# rfmacpower.net
KiCad netlist of a schematic drawn in EAGLE
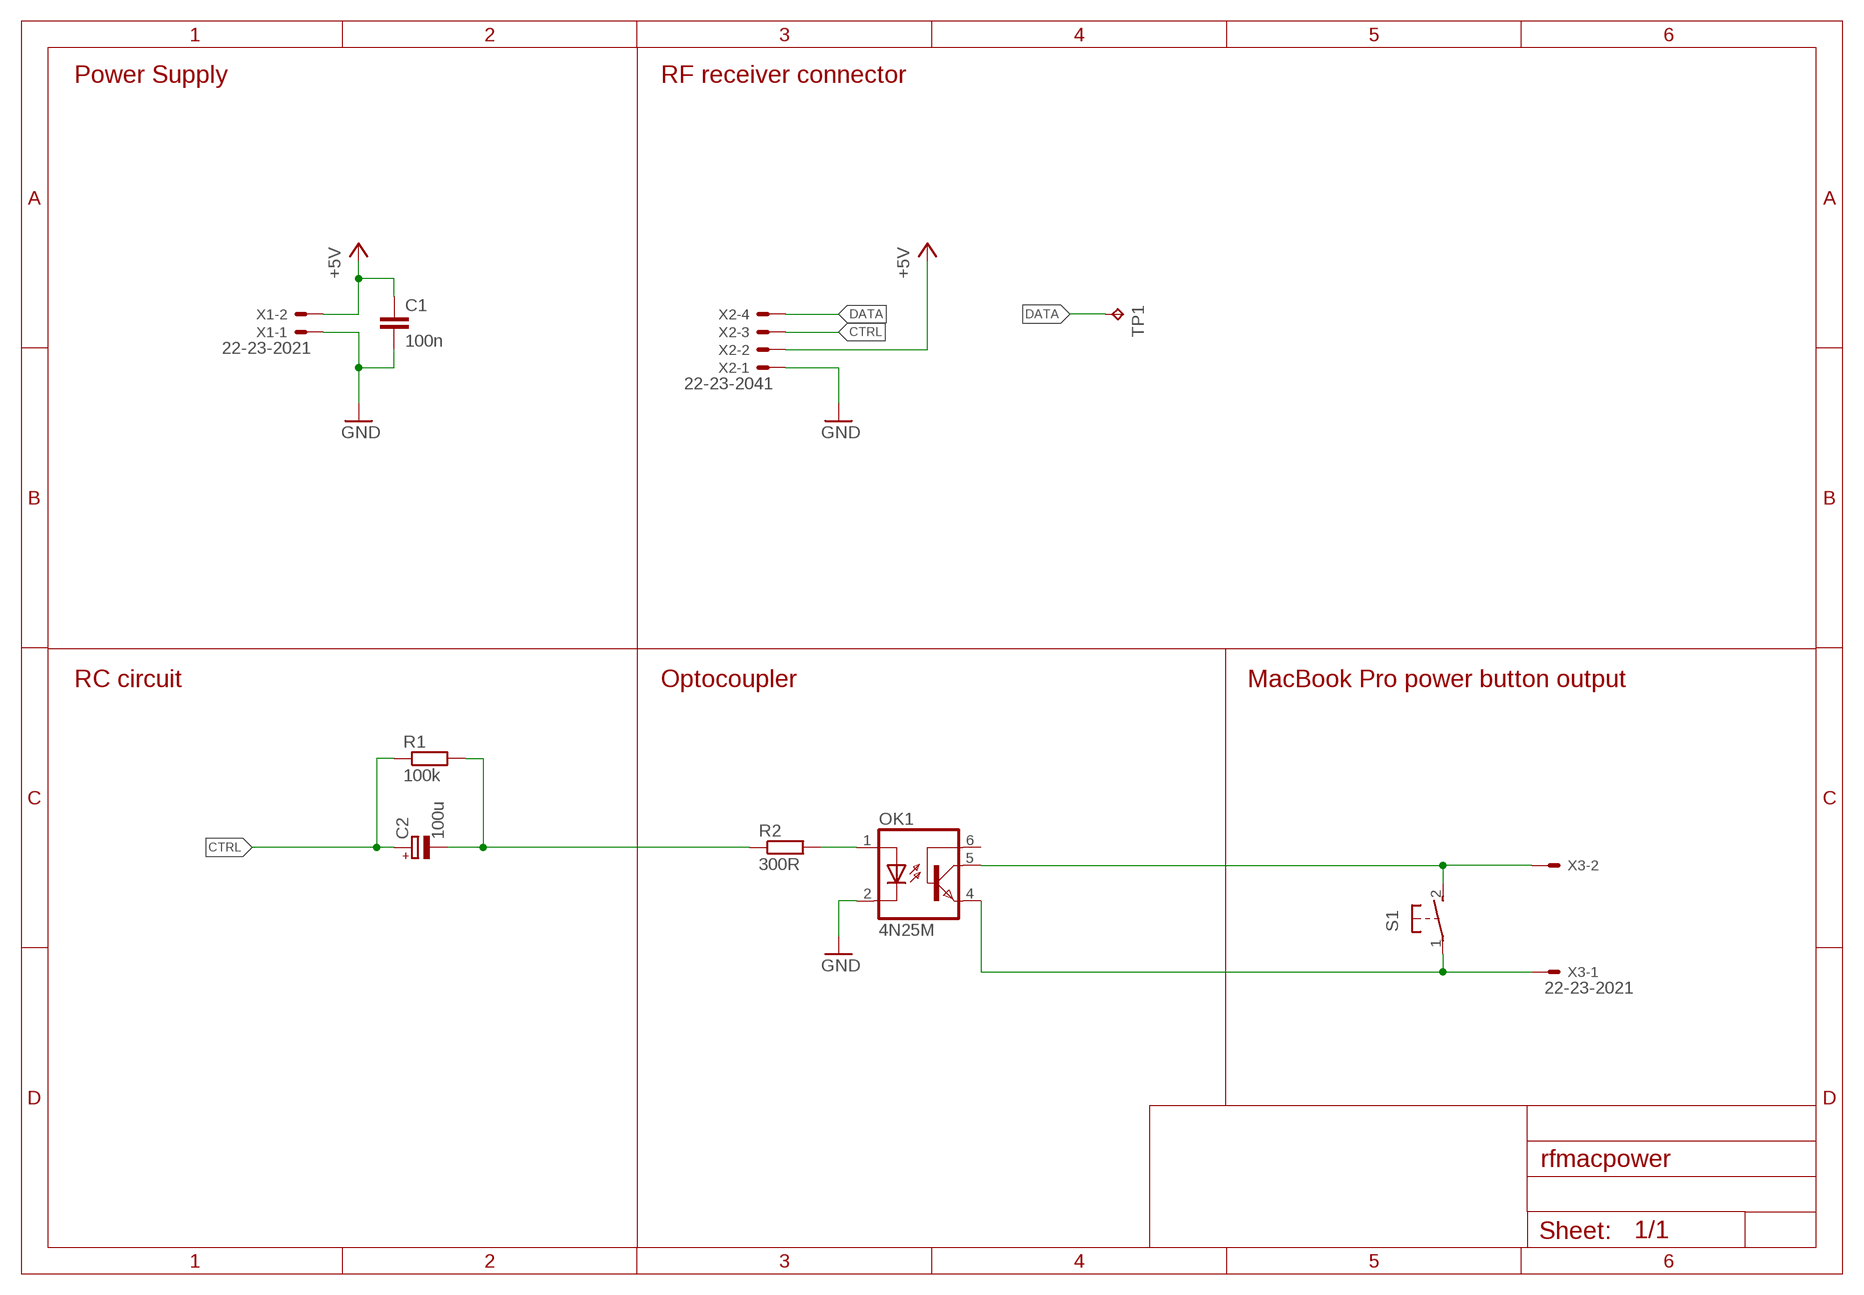
[diagram p0: schematic, sheet 1]

(export (version "E")
  (design (tool "Eeschema 10.0.6"))
  (components
    (comp (ref "C1")
      (value "100n")
      (footprint "eagle-import:C025-024X044")
      (libsource (lib "eagle-import") (part "C-EU025-024X044"))
    )
    (comp (ref "C2")
      (value "100u")
      (footprint "eagle-import:E2,5-7")
      (libsource (lib "eagle-import") (part "CPOL-EUE2.5-7"))
    )
    (comp (ref "OK1")
      (value "4N25M")
      (footprint "eagle-import:DIL06")
      (fields (field (name "MPN") "4N25-M"))
      (libsource (lib "eagle-import") (part "4N?M25"))
    )
    (comp (ref "R1")
      (value "100k")
      (footprint "eagle-import:0204_7")
      (libsource (lib "eagle-import") (part "R-EU_0204/7"))
    )
    (comp (ref "R2")
      (value "300R")
      (footprint "eagle-import:0204_7")
      (libsource (lib "eagle-import") (part "R-EU_0204/7"))
    )
    (comp (ref "S1")
      (value "DTS-3")
      (footprint "eagle-import:DTS-3")
      (libsource (lib "eagle-import") (part "DTS-3"))
    )
    (comp (ref "TP1")
      (value "TPPAD1-13")
      (footprint "eagle-import:P1-13")
      (libsource (lib "eagle-import") (part "TPPAD1-13"))
    )
    (comp (ref "X1")
      (value "22-23-2021")
      (footprint "eagle-import:22-23-2021")
      (fields (field (name "MF") "MOLEX"))
      (libsource (lib "eagle-import") (part "22-23-2021"))
    )
    (comp (ref "X2")
      (value "22-23-2041")
      (footprint "eagle-import:22-23-2041")
      (fields (field (name "MF") "MOLEX"))
      (libsource (lib "eagle-import") (part "22-23-2041"))
    )
    (comp (ref "X3")
      (value "22-23-2021")
      (footprint "eagle-import:22-23-2021")
      (fields (field (name "MF") "MOLEX"))
      (libsource (lib "eagle-import") (part "22-23-2021"))
    )
  )
  (nets
    (net (code "1") (name "+5V") (class "Default")
      (node (ref "C1") (pin "1") (pinfunction "1_1") (pintype "passive"))
      (node (ref "X1") (pin "2") (pinfunction "S_2") (pintype "passive"))
      (node (ref "X2") (pin "2") (pinfunction "S_2") (pintype "passive"))
    )
    (net (code "2") (name "CTRL") (class "Default")
      (node (ref "C2") (pin "+") (pinfunction "+_+") (pintype "passive"))
      (node (ref "R1") (pin "1") (pinfunction "1_1") (pintype "passive"))
      (node (ref "X2") (pin "3") (pinfunction "S_3") (pintype "passive"))
    )
    (net (code "3") (name "DATA") (class "Default")
      (node (ref "TP1") (pin "TP") (pinfunction "TP_TP") (pintype "input"))
      (node (ref "X2") (pin "4") (pinfunction "S_4") (pintype "passive"))
    )
    (net (code "4") (name "GND") (class "Default")
      (node (ref "C1") (pin "2") (pinfunction "2_2") (pintype "passive"))
      (node (ref "OK1") (pin "2") (pinfunction "C_2") (pintype "passive"))
      (node (ref "X1") (pin "1") (pinfunction "S_1") (pintype "passive"))
      (node (ref "X2") (pin "1") (pinfunction "S_1") (pintype "passive"))
    )
    (net (code "5") (name "Net-(C2-Pad-)") (class "Default")
      (node (ref "C2") (pin "-") (pinfunction "-_-") (pintype "passive"))
      (node (ref "R1") (pin "2") (pinfunction "2_2") (pintype "passive"))
      (node (ref "R2") (pin "1") (pinfunction "1_1") (pintype "passive"))
    )
    (net (code "6") (name "Net-(OK1-A)") (class "Default")
      (node (ref "OK1") (pin "1") (pinfunction "A_1") (pintype "passive"))
      (node (ref "R2") (pin "2") (pinfunction "2_2") (pintype "passive"))
    )
    (net (code "7") (name "Net-(OK1-COL)") (class "Default")
      (node (ref "OK1") (pin "5") (pinfunction "COL_5") (pintype "passive"))
      (node (ref "S1") (pin "2") (pinfunction "2_2") (pintype "passive"))
      (node (ref "X3") (pin "2") (pinfunction "S_2") (pintype "passive"))
    )
    (net (code "8") (name "Net-(OK1-EMI)") (class "Default")
      (node (ref "OK1") (pin "4") (pinfunction "EMI_4") (pintype "passive"))
      (node (ref "S1") (pin "1") (pinfunction "1_1") (pintype "passive"))
      (node (ref "X3") (pin "1") (pinfunction "S_1") (pintype "passive"))
    )
    (net (code "9") (name "unconnected-(OK1-BAS-Pad6)") (class "Default")
      (node (ref "OK1") (pin "6") (pinfunction "BAS_6") (pintype "passive"))
    )
  )
)
